# standalone.net
KiCad netlist of a schematic drawn in EAGLE
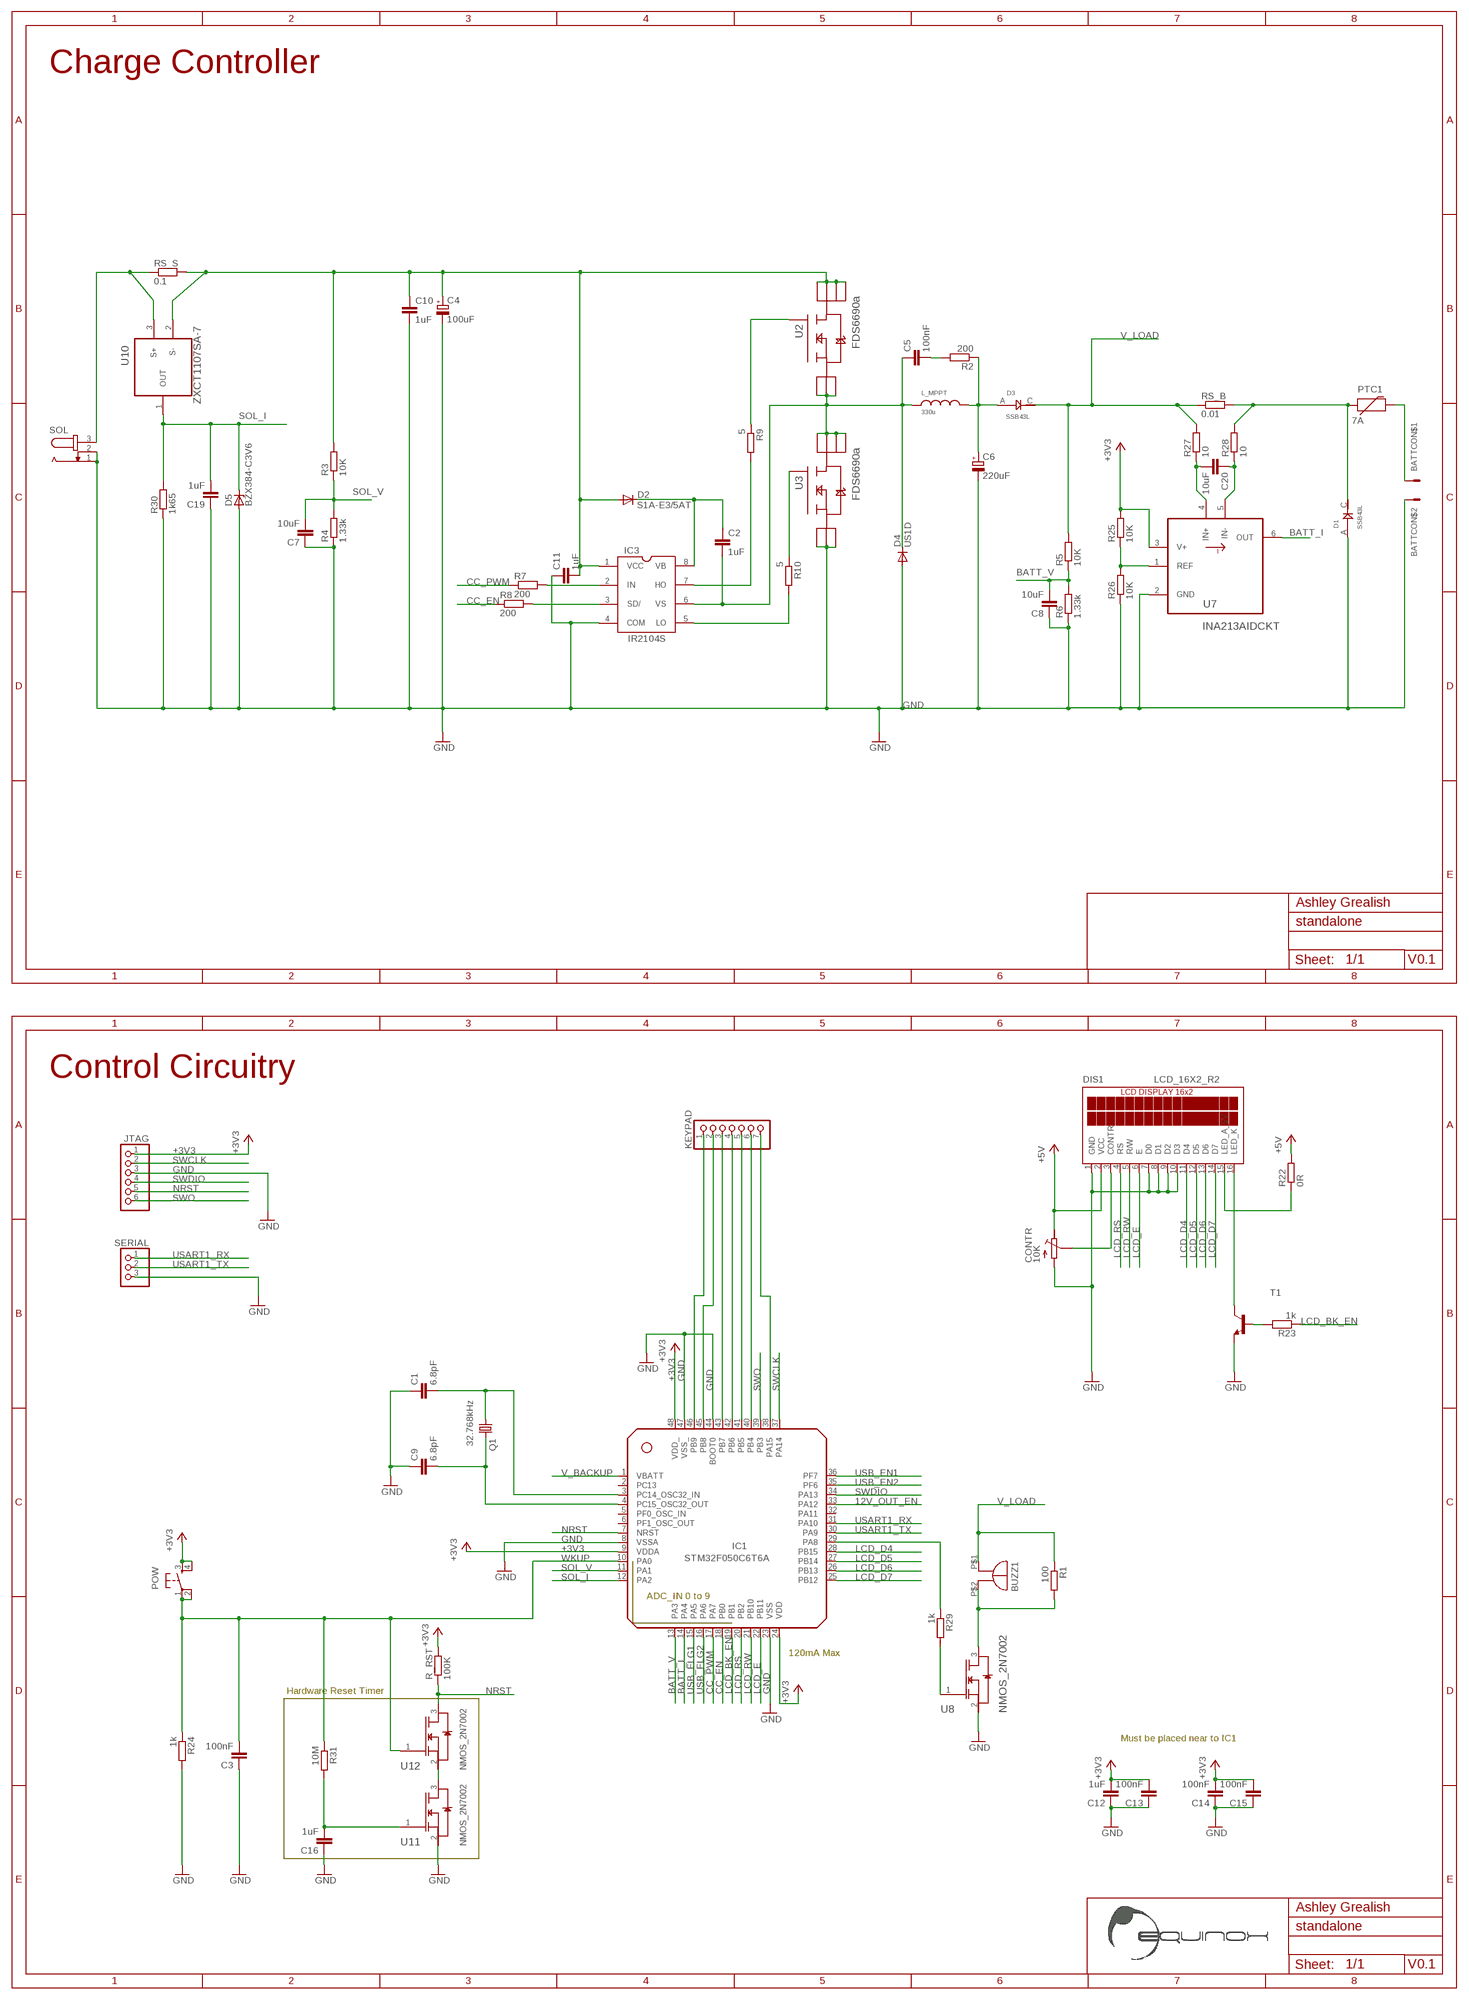
[diagram p0: schematic, sheet 1, part 1 of 2]
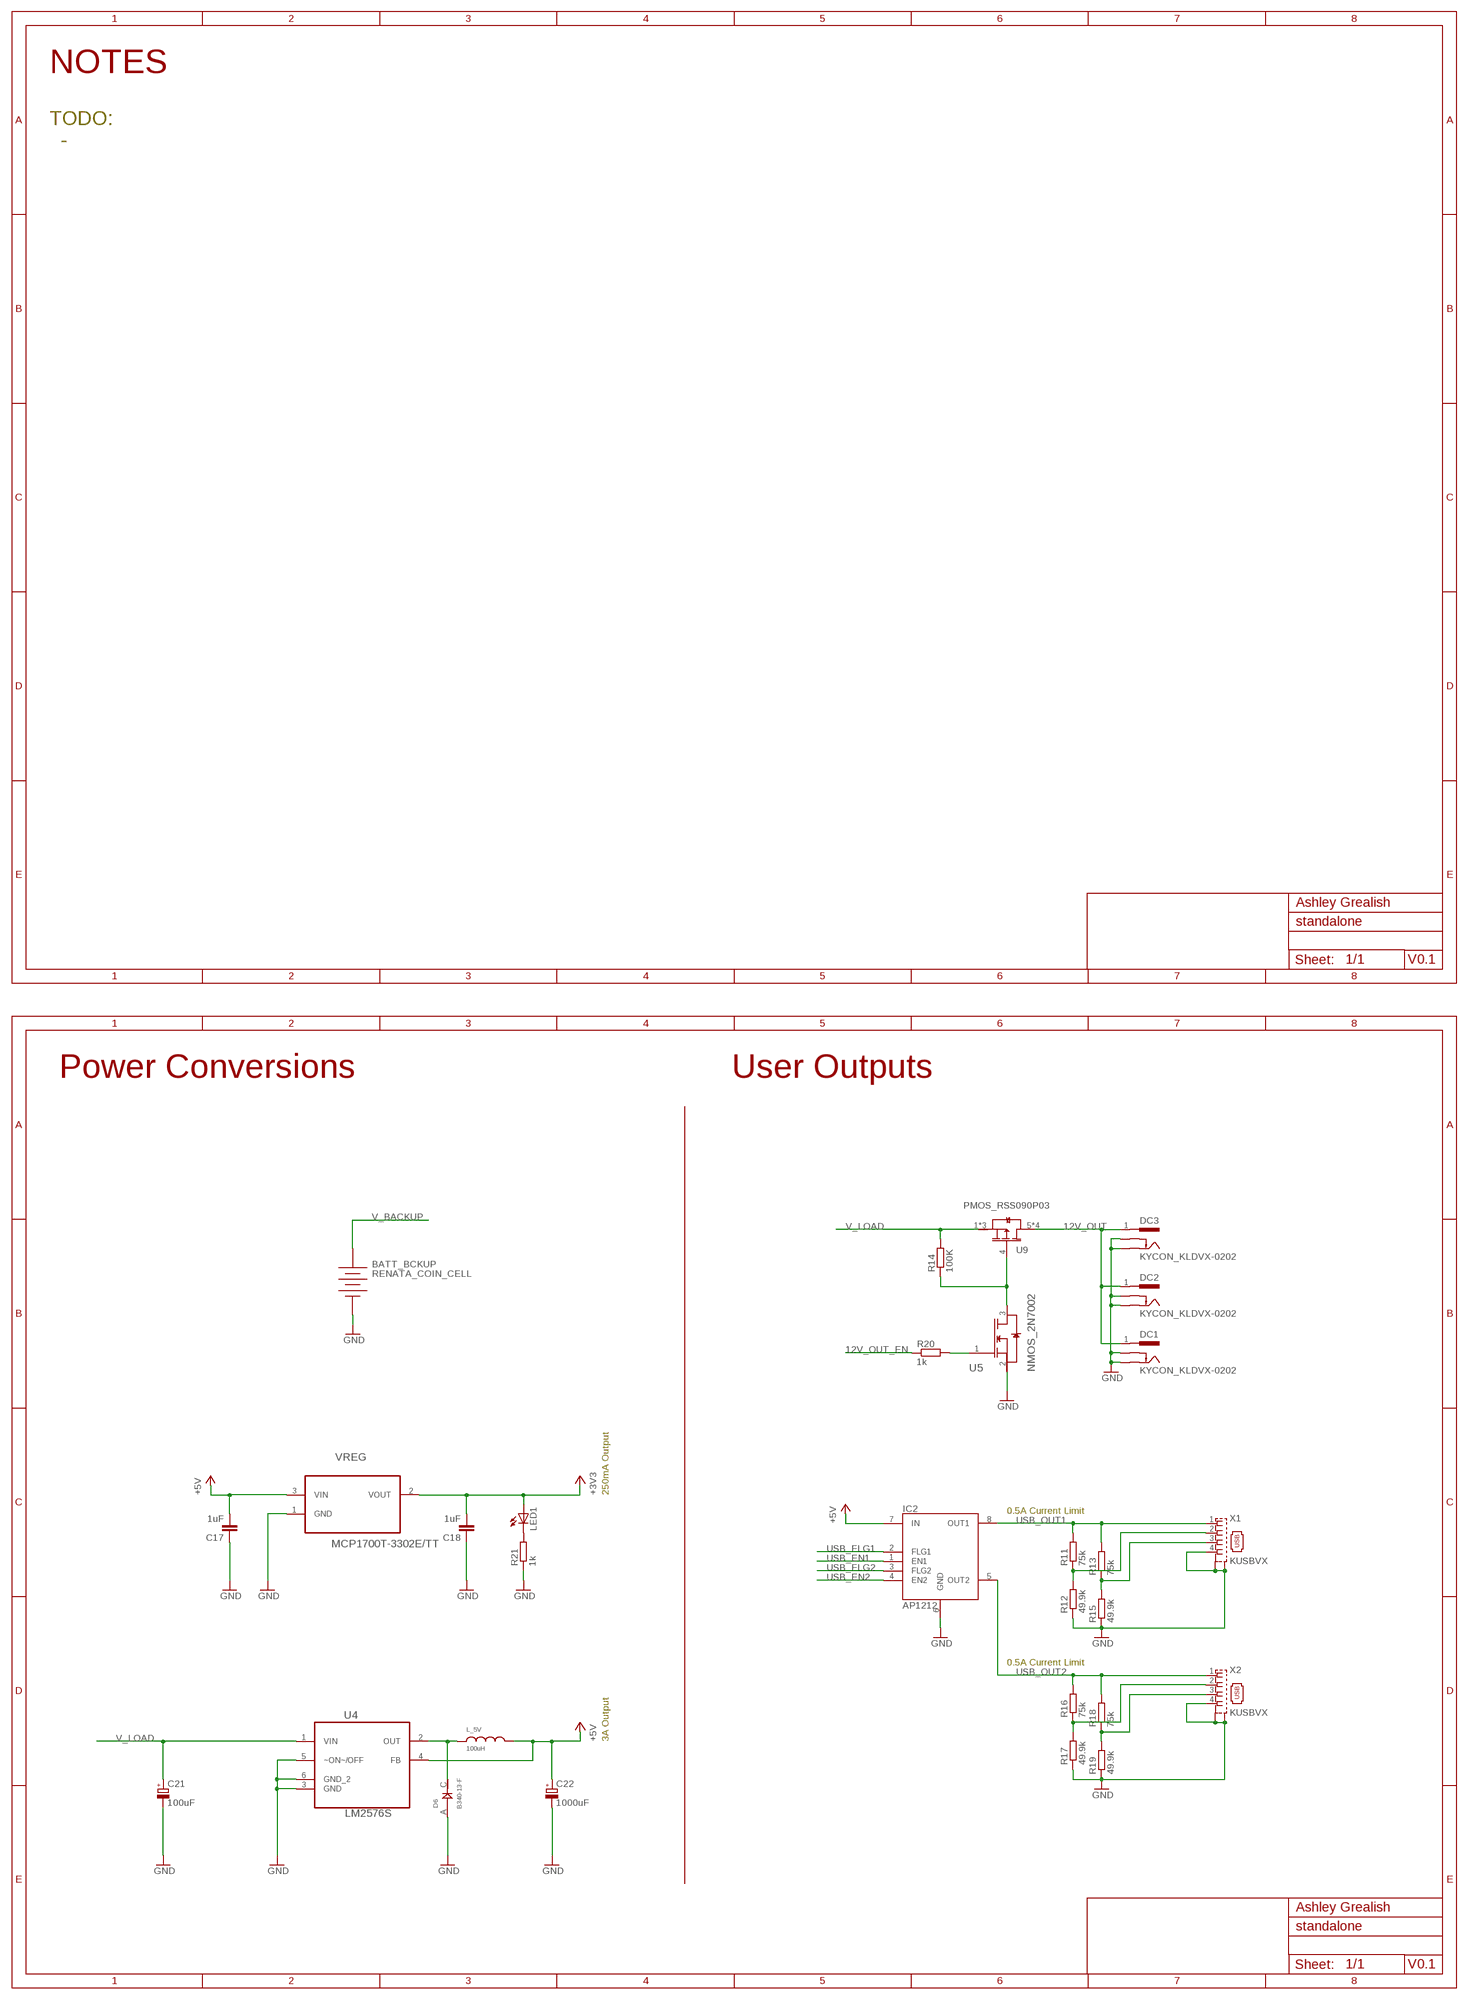
[diagram p1: schematic, sheet 1, part 2 of 2]

(export (version "E")
  (design (tool "Eeschema 10.0.6"))
  (components
    (comp (ref "BATT")
      (value "CON_MOLEX_39_29_1028")
      (footprint "eagle-import:MOLEX_39_29_1028")
      (fields (field (name "OC_FARNELL") "1012166"))
      (libsource (lib "eagle-import") (part "CON_MOLEX_39_29_1028"))
    )
    (comp (ref "BATT_BCKUP")
      (value "RENATA_COIN_CELL")
      (footprint "eagle-import:PANASONIC_CR2032_1298246")
      (libsource (lib "eagle-import") (part "PANASONIC_CR2032_1298246"))
    )
    (comp (ref "BUZZ1")
      (value "BUZZ_14MM")
      (footprint "eagle-import:BUZZ_14MM_5M_PINS")
      (libsource (lib "eagle-import") (part "BUZZ_14MM"))
    )
    (comp (ref "C1")
      (value "6.8pF")
      (footprint "eagle-import:C0603K")
      (libsource (lib "eagle-import") (part "C-EUC0603K"))
    )
    (comp (ref "C2")
      (value "1uF")
      (footprint "eagle-import:C0805K")
      (libsource (lib "eagle-import") (part "C-EUC0805K"))
    )
    (comp (ref "C3")
      (value "100nF")
      (footprint "eagle-import:C0805K")
      (libsource (lib "eagle-import") (part "C-EUC0805K"))
    )
    (comp (ref "C4")
      (value "100uF")
      (footprint "eagle-import:PANASONIC_E")
      (libsource (lib "eagle-import") (part "CPOL-EUE"))
    )
    (comp (ref "C5")
      (value "100nF")
      (footprint "eagle-import:C0805K")
      (libsource (lib "eagle-import") (part "C-EUC0805K"))
    )
    (comp (ref "C6")
      (value "220uF")
      (footprint "eagle-import:PANASONIC_F")
      (libsource (lib "eagle-import") (part "CPOL-EUF"))
    )
    (comp (ref "C7")
      (value "10uF")
      (footprint "eagle-import:C0805K")
      (libsource (lib "eagle-import") (part "C-EUC0805K"))
    )
    (comp (ref "C8")
      (value "10uF")
      (footprint "eagle-import:C0805K")
      (libsource (lib "eagle-import") (part "C-EUC0805K"))
    )
    (comp (ref "C9")
      (value "6.8pF")
      (footprint "eagle-import:C0603K")
      (libsource (lib "eagle-import") (part "C-EUC0603K"))
    )
    (comp (ref "C10")
      (value "1uF")
      (footprint "eagle-import:C0805K")
      (libsource (lib "eagle-import") (part "C-EUC0805K"))
    )
    (comp (ref "C11")
      (value "1uF")
      (footprint "eagle-import:C0805K")
      (libsource (lib "eagle-import") (part "C-EUC0805K"))
    )
    (comp (ref "C12")
      (value "1uF")
      (footprint "eagle-import:C0805K")
      (libsource (lib "eagle-import") (part "C-EUC0805K"))
    )
    (comp (ref "C13")
      (value "100nF")
      (footprint "eagle-import:C0805K")
      (libsource (lib "eagle-import") (part "C-EUC0805K"))
    )
    (comp (ref "C14")
      (value "100nF")
      (footprint "eagle-import:C0805K")
      (libsource (lib "eagle-import") (part "C-EUC0805K"))
    )
    (comp (ref "C15")
      (value "100nF")
      (footprint "eagle-import:C0805K")
      (libsource (lib "eagle-import") (part "C-EUC0805K"))
    )
    (comp (ref "C16")
      (value "1uF")
      (footprint "eagle-import:C0805K")
      (libsource (lib "eagle-import") (part "C-EUC0805K"))
    )
    (comp (ref "C17")
      (value "1uF")
      (footprint "eagle-import:C0805K")
      (libsource (lib "eagle-import") (part "C-EUC0805K"))
    )
    (comp (ref "C18")
      (value "1uF")
      (footprint "eagle-import:C0805K")
      (libsource (lib "eagle-import") (part "C-EUC0805K"))
    )
    (comp (ref "C19")
      (value "1uF")
      (footprint "eagle-import:C0805K")
      (libsource (lib "eagle-import") (part "C-EUC0805K"))
    )
    (comp (ref "C20")
      (value "10uF")
      (footprint "eagle-import:C0805K")
      (libsource (lib "eagle-import") (part "C-EUC0805K"))
    )
    (comp (ref "C21")
      (value "100uF")
      (footprint "eagle-import:PANASONIC_E")
      (libsource (lib "eagle-import") (part "CPOL-EUE"))
    )
    (comp (ref "C22")
      (value "1000uF")
      (footprint "eagle-import:PANASONIC_G")
      (libsource (lib "eagle-import") (part "CPOL-EUG"))
    )
    (comp (ref "CONTR")
      (value "10K")
      (footprint "eagle-import:R_TRIMM_RC33X")
      (libsource (lib "eagle-import") (part "R_TRIMM_TC33X"))
    )
    (comp (ref "D1")
      (value "SSB43L")
      (footprint "eagle-import:DO214AA")
      (libsource (lib "eagle-import") (part "DIODE_SSB43L"))
    )
    (comp (ref "D2")
      (value "S1A-E3/5AT")
      (footprint "eagle-import:DO-214AC")
      (libsource (lib "eagle-import") (part "DIODE-DO-214AC"))
    )
    (comp (ref "D3")
      (value "SSB43L")
      (footprint "eagle-import:DO214AA")
      (libsource (lib "eagle-import") (part "DIODE_SSB43L"))
    )
    (comp (ref "D4")
      (value "US1D")
      (footprint "eagle-import:DO-214AC")
      (libsource (lib "eagle-import") (part "DIODE-DO-214AC"))
    )
    (comp (ref "D5")
      (value "BZX384-C3V6")
      (footprint "eagle-import:SOD323")
      (libsource (lib "eagle-import") (part "BZX384-C3V6"))
    )
    (comp (ref "D6")
      (value "B340-13-F")
      (footprint "eagle-import:SMC")
      (libsource (lib "eagle-import") (part "DIODE_B340-13-F"))
    )
    (comp (ref "DC1")
      (value "KYCON_KLDVX-0202")
      (footprint "eagle-import:KYCON_KLVDX_2020_B")
      (libsource (lib "eagle-import") (part "KYCON_KLDVX-0202"))
    )
    (comp (ref "DC2")
      (value "KYCON_KLDVX-0202")
      (footprint "eagle-import:KYCON_KLVDX_2020_B")
      (libsource (lib "eagle-import") (part "KYCON_KLDVX-0202"))
    )
    (comp (ref "DC3")
      (value "KYCON_KLDVX-0202")
      (footprint "eagle-import:KYCON_KLVDX_2020_B")
      (libsource (lib "eagle-import") (part "KYCON_KLDVX-0202"))
    )
    (comp (ref "DIS1")
      (value "LCD_16X2_R2")
      (footprint "eagle-import:LCD_16X2_R2")
      (libsource (lib "eagle-import") (part "LCD_16X2_R2"))
    )
    (comp (ref "IC1")
      (value "STM32F050C6T6A")
      (footprint "eagle-import:LQFP48")
      (libsource (lib "eagle-import") (part "STM32F050C6T6A"))
    )
    (comp (ref "IC2")
      (value "AP1212")
      (footprint "eagle-import:SO8")
      (libsource (lib "eagle-import") (part "AP1212"))
    )
    (comp (ref "IC3")
      (value "IR2104S")
      (footprint "eagle-import:IR2104S")
      (libsource (lib "eagle-import") (part "IR2104S"))
    )
    (comp (ref "JTAG")
      (value "PINHD-1X6")
      (footprint "eagle-import:1X06")
      (libsource (lib "eagle-import") (part "PINHD-1X6"))
    )
    (comp (ref "KEYPAD")
      (value "PINHD-1X7/90")
      (footprint "eagle-import:1X07_90")
      (libsource (lib "eagle-import") (part "PINHD-1X7/90"))
    )
    (comp (ref "LED1")
      (value "POW_3V3")
      (footprint "eagle-import:CHIPLED_0805")
      (libsource (lib "eagle-import") (part "LEDCHIPLED_0805"))
    )
    (comp (ref "L_5V")
      (value "100uH")
      (footprint "eagle-import:INDUC_BOURNS_SDR2207")
      (libsource (lib "eagle-import") (part "INDUC_BOURNES_SDR2207"))
    )
    (comp (ref "L_MPPT")
      (value "330u")
      (footprint "eagle-import:INDUC_BOURNS_SDR1806")
      (libsource (lib "eagle-import") (part "INDUC_BOURNES_SDR1806"))
    )
    (comp (ref "POW")
      (value "TAC_SWITCHPTH")
      (footprint "eagle-import:TACTILE-PTH")
      (libsource (lib "eagle-import") (part "TAC_SWITCHPTH"))
    )
    (comp (ref "PTC1")
      (value "7A")
      (footprint "eagle-import:PTC_MF_R700")
      (libsource (lib "eagle-import") (part "PTC_MF_R700"))
    )
    (comp (ref "Q1")
      (value "32.768kHz")
      (footprint "eagle-import:MC-306")
      (fields
        (field (name "MPN") "MC-306 60.0KHZ  100PPM ,12.5PF")
        (field (name "MPN_1") "MC-306")
        (field (name "OC_FARNELL") "1712823")
        (field (name "OC_NEWARK") "-")
      )
      (libsource (lib "eagle-import") (part "MC-306"))
    )
    (comp (ref "R1")
      (value "100")
      (footprint "eagle-import:M0805")
      (libsource (lib "eagle-import") (part "resistor_R-EU_M0805"))
    )
    (comp (ref "R2")
      (value "200")
      (footprint "eagle-import:M0805")
      (libsource (lib "eagle-import") (part "R-EU_M0805"))
    )
    (comp (ref "R3")
      (value "10K")
      (footprint "eagle-import:M0805")
      (libsource (lib "eagle-import") (part "R-EU_M0805"))
    )
    (comp (ref "R4")
      (value "1.33k")
      (footprint "eagle-import:M0805")
      (libsource (lib "eagle-import") (part "R-EU_M0805"))
    )
    (comp (ref "R5")
      (value "10K")
      (footprint "eagle-import:M0805")
      (libsource (lib "eagle-import") (part "R-EU_M0805"))
    )
    (comp (ref "R6")
      (value "1.33k")
      (footprint "eagle-import:M0805")
      (libsource (lib "eagle-import") (part "R-EU_M0805"))
    )
    (comp (ref "R7")
      (value "200")
      (footprint "eagle-import:M0805")
      (libsource (lib "eagle-import") (part "R-EU_M0805"))
    )
    (comp (ref "R8")
      (value "200")
      (footprint "eagle-import:M0805")
      (libsource (lib "eagle-import") (part "R-EU_M0805"))
    )
    (comp (ref "R9")
      (value "5")
      (footprint "eagle-import:M0805")
      (libsource (lib "eagle-import") (part "R-EU_M0805"))
    )
    (comp (ref "R10")
      (value "5")
      (footprint "eagle-import:M0805")
      (libsource (lib "eagle-import") (part "R-EU_M0805"))
    )
    (comp (ref "R11")
      (value "75k")
      (footprint "eagle-import:M0805")
      (libsource (lib "eagle-import") (part "resistor_R-EU_M0805"))
    )
    (comp (ref "R12")
      (value "49.9k")
      (footprint "eagle-import:M0805")
      (libsource (lib "eagle-import") (part "resistor_R-EU_M0805"))
    )
    (comp (ref "R13")
      (value "75k")
      (footprint "eagle-import:M0805")
      (libsource (lib "eagle-import") (part "resistor_R-EU_M0805"))
    )
    (comp (ref "R14")
      (value "100K")
      (footprint "eagle-import:M0805")
      (libsource (lib "eagle-import") (part "R-EU_M0805"))
    )
    (comp (ref "R15")
      (value "49.9k")
      (footprint "eagle-import:M0805")
      (libsource (lib "eagle-import") (part "resistor_R-EU_M0805"))
    )
    (comp (ref "R16")
      (value "75k")
      (footprint "eagle-import:M0805")
      (libsource (lib "eagle-import") (part "resistor_R-EU_M0805"))
    )
    (comp (ref "R17")
      (value "49.9k")
      (footprint "eagle-import:M0805")
      (libsource (lib "eagle-import") (part "resistor_R-EU_M0805"))
    )
    (comp (ref "R18")
      (value "75k")
      (footprint "eagle-import:M0805")
      (libsource (lib "eagle-import") (part "resistor_R-EU_M0805"))
    )
    (comp (ref "R19")
      (value "49.9k")
      (footprint "eagle-import:M0805")
      (libsource (lib "eagle-import") (part "resistor_R-EU_M0805"))
    )
    (comp (ref "R20")
      (value "1k")
      (footprint "eagle-import:M0805")
      (libsource (lib "eagle-import") (part "R-EU_M0805"))
    )
    (comp (ref "R21")
      (value "1k")
      (footprint "eagle-import:M0805")
      (libsource (lib "eagle-import") (part "resistor_R-EU_M0805"))
    )
    (comp (ref "R22")
      (value "0R")
      (footprint "eagle-import:M0805")
      (libsource (lib "eagle-import") (part "resistor_R-EU_M0805"))
    )
    (comp (ref "R23")
      (value "1k")
      (footprint "eagle-import:M0805")
      (libsource (lib "eagle-import") (part "resistor_R-EU_M0805"))
    )
    (comp (ref "R24")
      (value "1k")
      (footprint "eagle-import:M0805")
      (libsource (lib "eagle-import") (part "resistor_R-EU_M0805"))
    )
    (comp (ref "R25")
      (value "10K")
      (footprint "eagle-import:M0805")
      (libsource (lib "eagle-import") (part "R-EU_M0805"))
    )
    (comp (ref "R26")
      (value "10K")
      (footprint "eagle-import:M0805")
      (libsource (lib "eagle-import") (part "R-EU_M0805"))
    )
    (comp (ref "R27")
      (value "10")
      (footprint "eagle-import:M0805")
      (libsource (lib "eagle-import") (part "R-EU_M0805"))
    )
    (comp (ref "R28")
      (value "10")
      (footprint "eagle-import:M0805")
      (libsource (lib "eagle-import") (part "R-EU_M0805"))
    )
    (comp (ref "R29")
      (value "1k")
      (footprint "eagle-import:M0805")
      (libsource (lib "eagle-import") (part "resistor_R-EU_M0805"))
    )
    (comp (ref "R30")
      (value "1k65")
      (footprint "eagle-import:M0805")
      (libsource (lib "eagle-import") (part "R-EU_M0805"))
    )
    (comp (ref "R31")
      (value "10M")
      (footprint "eagle-import:M0805")
      (libsource (lib "eagle-import") (part "resistor_R-EU_M0805"))
    )
    (comp (ref "RS_B")
      (value "0.01")
      (footprint "eagle-import:R2512")
      (libsource (lib "eagle-import") (part "R-EU_R2512"))
    )
    (comp (ref "RS_S")
      (value "0.1")
      (footprint "eagle-import:R2512")
      (libsource (lib "eagle-import") (part "R-EU_R2512"))
    )
    (comp (ref "R_RST")
      (value "100K")
      (footprint "eagle-import:M0805")
      (libsource (lib "eagle-import") (part "R-EU_M0805"))
    )
    (comp (ref "SERIAL")
      (value "PINHD-1X3")
      (footprint "eagle-import:1X03")
      (libsource (lib "eagle-import") (part "PINHD-1X3"))
    )
    (comp (ref "SOL")
      (value "JACK-PLUG0")
      (footprint "eagle-import:SPC4077")
      (libsource (lib "eagle-import") (part "JACK-PLUG0"))
    )
    (comp (ref "T1")
      (value "BC847B-NPN-SOT23-BEC")
      (footprint "eagle-import:SOT23-BEC")
      (libsource (lib "eagle-import") (part "-NPN-SOT23-BECBC847B"))
    )
    (comp (ref "U$1")
      (value "EQUINOX_LOGO_LARGE")
      (footprint "eagle-import:EQUINOX_LOGO_LARGE")
      (libsource (lib "eagle-import") (part "EQUINOX_LOGO_LARGE"))
    )
    (comp (ref "U2")
      (value "FDS6690a")
      (footprint "eagle-import:SOIC127P600X175-8N")
      (fields (field (name "MPN") "DMS3016SSS-13") (field (name "OC_FARNELL") "9845275"))
      (libsource (lib "eagle-import") (part "DMS3016SSS-13"))
    )
    (comp (ref "U3")
      (value "FDS6690a")
      (footprint "eagle-import:SOIC127P600X175-8N")
      (fields (field (name "MPN") "DMS3016SSS-13") (field (name "OC_FARNELL") "9845275 "))
      (libsource (lib "eagle-import") (part "DMS3016SSS-13"))
    )
    (comp (ref "U4")
      (value "LM2576S")
      (footprint "eagle-import:TO263-5")
      (libsource (lib "eagle-import") (part "LM2576S"))
    )
    (comp (ref "U5")
      (value "NMOS_2N7002")
      (footprint "eagle-import:SOT103P240X110-3N")
      (fields (field (name "MPN") "2N7002-7-F"))
      (libsource (lib "eagle-import") (part "NMOS_2N7002"))
    )
    (comp (ref "U7")
      (value "INA213AIDCKT")
      (footprint "eagle-import:SOT65P210X110-6N")
      (libsource (lib "eagle-import") (part "INA213AIDCKT"))
    )
    (comp (ref "U8")
      (value "NMOS_2N7002")
      (footprint "eagle-import:SOT103P240X110-3N")
      (fields
        (field (name "MPN") "2N7002-7-F")
        (field (name "MPN_1") "2N7002-7-F")
        (field (name "OC_FARNELL") "1713823")
        (field (name "OC_NEWARK") "25R5679")
        (field (name "PACKAGE") "SOT-23-3")
        (field (name "SUPPLIER") "DIODES INC.")
      )
      (libsource (lib "eagle-import") (part "NMOS_2N7002"))
    )
    (comp (ref "U9")
      (value "PMOS_RSS090P03")
      (footprint "eagle-import:SO8")
      (libsource (lib "eagle-import") (part "PMOS_RSS090P03"))
    )
    (comp (ref "U10")
      (value "ZXCT1107SA-7")
      (footprint "eagle-import:SOT91P240X110-3N")
      (libsource (lib "eagle-import") (part "ZXCT1107SA-7"))
    )
    (comp (ref "U11")
      (value "NMOS_2N7002")
      (footprint "eagle-import:SOT103P240X110-3N")
      (fields
        (field (name "MPN") "2N7002-7-F")
        (field (name "MPN_1") "2N7002-7-F")
        (field (name "OC_FARNELL") "1713823")
        (field (name "OC_NEWARK") "25R5679")
        (field (name "PACKAGE") "SOT-23-3")
        (field (name "SUPPLIER") "DIODES INC.")
      )
      (libsource (lib "eagle-import") (part "NMOS_2N7002"))
    )
    (comp (ref "U12")
      (value "NMOS_2N7002")
      (footprint "eagle-import:SOT103P240X110-3N")
      (fields
        (field (name "MPN") "2N7002-7-F")
        (field (name "MPN_1") "2N7002-7-F")
        (field (name "OC_FARNELL") "1713823")
        (field (name "OC_NEWARK") "25R5679")
        (field (name "PACKAGE") "SOT-23-3")
        (field (name "SUPPLIER") "DIODES INC.")
      )
      (libsource (lib "eagle-import") (part "NMOS_2N7002"))
    )
    (comp (ref "VREG")
      (value "MCP1700T-3302E/TT")
      (footprint "eagle-import:SOT95P237X112-3N")
      (libsource (lib "eagle-import") (part "MCP1700T-3302E/TT"))
    )
    (comp (ref "X1")
      (value "KUSBVX")
      (footprint "eagle-import:KUSBVX")
      (libsource (lib "eagle-import") (part "KUSBVX"))
    )
    (comp (ref "X2")
      (value "KUSBVX")
      (footprint "eagle-import:KUSBVX")
      (libsource (lib "eagle-import") (part "KUSBVX"))
    )
  )
  (nets
    (net (code "1") (name "+3V3") (class "Default")
      (node (ref "C12") (pin "2") (pinfunction "2_2") (pintype "passive"))
      (node (ref "C13") (pin "2") (pinfunction "2_2") (pintype "passive"))
      (node (ref "C14") (pin "2") (pinfunction "2_2") (pintype "passive"))
      (node (ref "C15") (pin "2") (pinfunction "2_2") (pintype "passive"))
      (node (ref "C18") (pin "2") (pinfunction "2_2") (pintype "passive"))
      (node (ref "IC1") (pin "24") (pinfunction "VDD_24") (pintype "power_in"))
      (node (ref "IC1") (pin "48") (pinfunction "VDD__48") (pintype "power_in"))
      (node (ref "IC1") (pin "9") (pinfunction "VDDA_9") (pintype "bidirectional"))
      (node (ref "JTAG") (pin "1") (pinfunction "1_1") (pintype "passive"))
      (node (ref "LED1") (pin "A") (pinfunction "A_A") (pintype "passive"))
      (node (ref "POW") (pin "3") (pinfunction "3_3") (pintype "passive"))
      (node (ref "POW") (pin "4") (pinfunction "4_4") (pintype "passive"))
      (node (ref "R25") (pin "2") (pinfunction "2_2") (pintype "passive"))
      (node (ref "R_RST") (pin "2") (pinfunction "2_2") (pintype "passive"))
      (node (ref "U7") (pin "3") (pinfunction "V+_3") (pintype "power_in"))
      (node (ref "VREG") (pin "2") (pinfunction "VOUT_2") (pintype "output"))
    )
    (net (code "2") (name "+5V") (class "Default")
      (node (ref "C17") (pin "2") (pinfunction "2_2") (pintype "passive"))
      (node (ref "C22") (pin "+") (pinfunction "+_+") (pintype "passive"))
      (node (ref "CONTR") (pin "CW") (pinfunction "A_CW") (pintype "passive"))
      (node (ref "DIS1") (pin "2") (pinfunction "VCC_2") (pintype "power_in"))
      (node (ref "IC2") (pin "7") (pinfunction "IN_7") (pintype "bidirectional"))
      (node (ref "L_5V") (pin "P$2") (pinfunction "P$2_P$2") (pintype "bidirectional"))
      (node (ref "R22") (pin "2") (pinfunction "2_2") (pintype "passive"))
      (node (ref "U4") (pin "4") (pinfunction "FB_4") (pintype "bidirectional"))
      (node (ref "VREG") (pin "3") (pinfunction "VIN_3") (pintype "input"))
    )
    (net (code "3") (name "/12V_OUT") (class "Default")
      (node (ref "DC1") (pin "1") (pinfunction "PAD1_1") (pintype "passive"))
      (node (ref "DC2") (pin "1") (pinfunction "PAD1_1") (pintype "passive"))
      (node (ref "DC3") (pin "1") (pinfunction "PAD1_1") (pintype "passive"))
      (node (ref "U9") (pin "5") (pinfunction "D2_5") (pintype "bidirectional"))
      (node (ref "U9") (pin "6") (pinfunction "D2_6") (pintype "bidirectional"))
      (node (ref "U9") (pin "7") (pinfunction "D2_7") (pintype "bidirectional"))
      (node (ref "U9") (pin "8") (pinfunction "D2_8") (pintype "bidirectional"))
    )
    (net (code "4") (name "/12V_OUT_EN") (class "Default")
      (node (ref "IC1") (pin "33") (pinfunction "PA12_33") (pintype "bidirectional"))
      (node (ref "R20") (pin "1") (pinfunction "1_1") (pintype "passive"))
    )
    (net (code "5") (name "/BATT_I") (class "Default")
      (node (ref "IC1") (pin "14") (pinfunction "PA4_14") (pintype "bidirectional"))
      (node (ref "U7") (pin "6") (pinfunction "OUT_6") (pintype "output"))
    )
    (net (code "6") (name "/BATT_V") (class "Default")
      (node (ref "C8") (pin "2") (pinfunction "2_2") (pintype "passive"))
      (node (ref "IC1") (pin "13") (pinfunction "PA3_13") (pintype "bidirectional"))
      (node (ref "R5") (pin "1") (pinfunction "1_1") (pintype "passive"))
      (node (ref "R6") (pin "2") (pinfunction "2_2") (pintype "passive"))
    )
    (net (code "7") (name "/CC_EN") (class "Default")
      (node (ref "IC1") (pin "18") (pinfunction "PB0_18") (pintype "bidirectional"))
      (node (ref "R8") (pin "1") (pinfunction "1_1") (pintype "passive"))
    )
    (net (code "8") (name "/CC_PWM") (class "Default")
      (node (ref "IC1") (pin "17") (pinfunction "PA7_17") (pintype "bidirectional"))
      (node (ref "R7") (pin "1") (pinfunction "1_1") (pintype "passive"))
    )
    (net (code "9") (name "/LCD_BK_EN") (class "Default")
      (node (ref "IC1") (pin "19") (pinfunction "PB1_19") (pintype "bidirectional"))
      (node (ref "R23") (pin "1") (pinfunction "1_1") (pintype "passive"))
    )
    (net (code "10") (name "/LCD_D4") (class "Default")
      (node (ref "DIS1") (pin "11") (pinfunction "D4_11") (pintype "input"))
      (node (ref "IC1") (pin "28") (pinfunction "PB15_28") (pintype "bidirectional"))
    )
    (net (code "11") (name "/LCD_D5") (class "Default")
      (node (ref "DIS1") (pin "12") (pinfunction "D5_12") (pintype "input"))
      (node (ref "IC1") (pin "27") (pinfunction "PB14_27") (pintype "bidirectional"))
    )
    (net (code "12") (name "/LCD_D6") (class "Default")
      (node (ref "DIS1") (pin "13") (pinfunction "D6_13") (pintype "input"))
      (node (ref "IC1") (pin "26") (pinfunction "PB13_26") (pintype "bidirectional"))
    )
    (net (code "13") (name "/LCD_D7") (class "Default")
      (node (ref "DIS1") (pin "14") (pinfunction "D7_14") (pintype "input"))
      (node (ref "IC1") (pin "25") (pinfunction "PB12_25") (pintype "bidirectional"))
    )
    (net (code "14") (name "/LCD_E") (class "Default")
      (node (ref "DIS1") (pin "6") (pinfunction "E_6") (pintype "input"))
      (node (ref "IC1") (pin "22") (pinfunction "PB11_22") (pintype "bidirectional"))
    )
    (net (code "15") (name "/LCD_RS") (class "Default")
      (node (ref "DIS1") (pin "4") (pinfunction "RS_4") (pintype "input"))
      (node (ref "IC1") (pin "20") (pinfunction "PB2_20") (pintype "bidirectional"))
    )
    (net (code "16") (name "/LCD_RW") (class "Default")
      (node (ref "DIS1") (pin "5") (pinfunction "R/W_5") (pintype "input"))
      (node (ref "IC1") (pin "21") (pinfunction "PB10_21") (pintype "bidirectional"))
    )
    (net (code "17") (name "/NRST") (class "Default")
      (node (ref "IC1") (pin "7") (pinfunction "NRST_7") (pintype "bidirectional"))
      (node (ref "JTAG") (pin "5") (pinfunction "5_5") (pintype "passive"))
      (node (ref "R_RST") (pin "1") (pinfunction "1_1") (pintype "passive"))
      (node (ref "U12") (pin "3") (pinfunction "D_3") (pintype "output"))
    )
    (net (code "18") (name "/SOL_I") (class "Default")
      (node (ref "C19") (pin "2") (pinfunction "2_2") (pintype "passive"))
      (node (ref "D5") (pin "C") (pinfunction "C_C") (pintype "passive"))
      (node (ref "IC1") (pin "12") (pinfunction "PA2_12") (pintype "bidirectional"))
      (node (ref "R30") (pin "2") (pinfunction "2_2") (pintype "passive"))
      (node (ref "U10") (pin "1") (pinfunction "OUT_1") (pintype "output"))
    )
    (net (code "19") (name "/SOL_V") (class "Default")
      (node (ref "C7") (pin "2") (pinfunction "2_2") (pintype "passive"))
      (node (ref "IC1") (pin "11") (pinfunction "PA1_11") (pintype "bidirectional"))
      (node (ref "R3") (pin "1") (pinfunction "1_1") (pintype "passive"))
      (node (ref "R4") (pin "2") (pinfunction "2_2") (pintype "passive"))
    )
    (net (code "20") (name "/SWCLK") (class "Default")
      (node (ref "IC1") (pin "37") (pinfunction "PA14_37") (pintype "bidirectional"))
      (node (ref "JTAG") (pin "2") (pinfunction "2_2") (pintype "passive"))
    )
    (net (code "21") (name "/SWDIO") (class "Default")
      (node (ref "IC1") (pin "34") (pinfunction "PA13_34") (pintype "bidirectional"))
      (node (ref "JTAG") (pin "4") (pinfunction "4_4") (pintype "passive"))
    )
    (net (code "22") (name "/SWO") (class "Default")
      (node (ref "IC1") (pin "39") (pinfunction "PB3_39") (pintype "bidirectional"))
      (node (ref "JTAG") (pin "6") (pinfunction "6_6") (pintype "passive"))
    )
    (net (code "23") (name "/USART1_RX") (class "Default")
      (node (ref "IC1") (pin "31") (pinfunction "PA10_31") (pintype "bidirectional"))
      (node (ref "SERIAL") (pin "1") (pinfunction "1_1") (pintype "passive"))
    )
    (net (code "24") (name "/USART1_TX") (class "Default")
      (node (ref "IC1") (pin "30") (pinfunction "PA9_30") (pintype "bidirectional"))
      (node (ref "SERIAL") (pin "2") (pinfunction "2_2") (pintype "passive"))
    )
    (net (code "25") (name "/USB_EN1") (class "Default")
      (node (ref "IC1") (pin "36") (pinfunction "PF7_36") (pintype "bidirectional"))
      (node (ref "IC2") (pin "1") (pinfunction "EN1_1") (pintype "bidirectional"))
    )
    (net (code "26") (name "/USB_EN2") (class "Default")
      (node (ref "IC1") (pin "35") (pinfunction "PF6_35") (pintype "bidirectional"))
      (node (ref "IC2") (pin "4") (pinfunction "EN2_4") (pintype "bidirectional"))
    )
    (net (code "27") (name "/USB_FLG1") (class "Default")
      (node (ref "IC1") (pin "15") (pinfunction "PA5_15") (pintype "bidirectional"))
      (node (ref "IC2") (pin "2") (pinfunction "FLG1_2") (pintype "bidirectional"))
    )
    (net (code "28") (name "/USB_FLG2") (class "Default")
      (node (ref "IC1") (pin "16") (pinfunction "PA6_16") (pintype "bidirectional"))
      (node (ref "IC2") (pin "3") (pinfunction "FLG2_3") (pintype "bidirectional"))
    )
    (net (code "29") (name "/USB_OUT1") (class "Default")
      (node (ref "IC2") (pin "8") (pinfunction "OUT1_8") (pintype "bidirectional"))
      (node (ref "R11") (pin "2") (pinfunction "2_2") (pintype "passive"))
      (node (ref "R13") (pin "2") (pinfunction "2_2") (pintype "passive"))
      (node (ref "X1") (pin "1") (pinfunction "1_1") (pintype "passive"))
    )
    (net (code "30") (name "/USB_OUT2") (class "Default")
      (node (ref "IC2") (pin "5") (pinfunction "OUT2_5") (pintype "bidirectional"))
      (node (ref "R16") (pin "2") (pinfunction "2_2") (pintype "passive"))
      (node (ref "R18") (pin "2") (pinfunction "2_2") (pintype "passive"))
      (node (ref "X2") (pin "1") (pinfunction "1_1") (pintype "passive"))
    )
    (net (code "31") (name "/V_BACKUP") (class "Default")
      (node (ref "BATT_BCKUP") (pin "P+") (pinfunction "POS_P+") (pintype "bidirectional"))
      (node (ref "IC1") (pin "1") (pinfunction "VBATT_1") (pintype "bidirectional"))
    )
    (net (code "32") (name "/V_LOAD") (class "Default")
      (node (ref "BUZZ1") (pin "P$1") (pinfunction "+_P$1") (pintype "passive"))
      (node (ref "C21") (pin "+") (pinfunction "+_+") (pintype "passive"))
      (node (ref "D3") (pin "C") (pinfunction "CATHODE_C") (pintype "bidirectional"))
      (node (ref "R1") (pin "1") (pinfunction "1_1") (pintype "passive"))
      (node (ref "R14") (pin "2") (pinfunction "2_2") (pintype "passive"))
      (node (ref "R27") (pin "2") (pinfunction "2_2") (pintype "passive"))
      (node (ref "R5") (pin "2") (pinfunction "2_2") (pintype "passive"))
      (node (ref "RS_B") (pin "1") (pinfunction "1_1") (pintype "passive"))
      (node (ref "U4") (pin "1") (pinfunction "VIN_1") (pintype "input"))
      (node (ref "U9") (pin "1") (pinfunction "S2_1") (pintype "bidirectional"))
      (node (ref "U9") (pin "2") (pinfunction "S2_2") (pintype "bidirectional"))
      (node (ref "U9") (pin "3") (pinfunction "S2_3") (pintype "bidirectional"))
    )
    (net (code "33") (name "/WKUP") (class "Default")
      (node (ref "C3") (pin "2") (pinfunction "2_2") (pintype "passive"))
      (node (ref "IC1") (pin "10") (pinfunction "PA0_10") (pintype "bidirectional"))
      (node (ref "POW") (pin "1") (pinfunction "1_1") (pintype "passive"))
      (node (ref "POW") (pin "2") (pinfunction "2_2") (pintype "passive"))
      (node (ref "R24") (pin "1") (pinfunction "1_1") (pintype "passive"))
      (node (ref "R31") (pin "1") (pinfunction "1_1") (pintype "passive"))
      (node (ref "U12") (pin "1") (pinfunction "G_1") (pintype "input"))
    )
    (net (code "34") (name "GND") (class "Default")
      (node (ref "BATT") (pin "P$2") (pinfunction "S_P$2") (pintype "passive"))
      (node (ref "BATT_BCKUP") (pin "P-") (pinfunction "NEG_P-") (pintype "bidirectional"))
      (node (ref "C1") (pin "1") (pinfunction "1_1") (pintype "passive"))
      (node (ref "C10") (pin "2") (pinfunction "2_2") (pintype "passive"))
      (node (ref "C11") (pin "1") (pinfunction "1_1") (pintype "passive"))
      (node (ref "C12") (pin "1") (pinfunction "1_1") (pintype "passive"))
      (node (ref "C13") (pin "1") (pinfunction "1_1") (pintype "passive"))
      (node (ref "C14") (pin "1") (pinfunction "1_1") (pintype "passive"))
      (node (ref "C15") (pin "1") (pinfunction "1_1") (pintype "passive"))
      (node (ref "C16") (pin "1") (pinfunction "1_1") (pintype "passive"))
      (node (ref "C17") (pin "1") (pinfunction "1_1") (pintype "passive"))
      (node (ref "C18") (pin "1") (pinfunction "1_1") (pintype "passive"))
      (node (ref "C19") (pin "1") (pinfunction "1_1") (pintype "passive"))
      (node (ref "C21") (pin "-") (pinfunction "-_-") (pintype "passive"))
      (node (ref "C22") (pin "-") (pinfunction "-_-") (pintype "passive"))
      (node (ref "C3") (pin "1") (pinfunction "1_1") (pintype "passive"))
      (node (ref "C4") (pin "-") (pinfunction "-_-") (pintype "passive"))
      (node (ref "C6") (pin "-") (pinfunction "-_-") (pintype "passive"))
      (node (ref "C7") (pin "1") (pinfunction "1_1") (pintype "passive"))
      (node (ref "C8") (pin "1") (pinfunction "1_1") (pintype "passive"))
      (node (ref "C9") (pin "1") (pinfunction "1_1") (pintype "passive"))
      (node (ref "CONTR") (pin "CCW") (pinfunction "E_CCW") (pintype "passive"))
      (node (ref "D1") (pin "A") (pinfunction "ANODE_A") (pintype "bidirectional"))
      (node (ref "D4") (pin "A") (pinfunction "A_A") (pintype "passive"))
      (node (ref "D5") (pin "A") (pinfunction "A_A") (pintype "passive"))
      (node (ref "D6") (pin "A") (pinfunction "ANODE_A") (pintype "bidirectional"))
      (node (ref "DC1") (pin "2") (pinfunction "PAD2_2") (pintype "passive"))
      (node (ref "DC1") (pin "3") (pinfunction "PAD3_3") (pintype "passive"))
      (node (ref "DC2") (pin "2") (pinfunction "PAD2_2") (pintype "passive"))
      (node (ref "DC2") (pin "3") (pinfunction "PAD3_3") (pintype "passive"))
      (node (ref "DC3") (pin "2") (pinfunction "PAD2_2") (pintype "passive"))
      (node (ref "DC3") (pin "3") (pinfunction "PAD3_3") (pintype "passive"))
      (node (ref "DIS1") (pin "1") (pinfunction "GND_1") (pintype "power_in"))
      (node (ref "DIS1") (pin "10") (pinfunction "D3_10") (pintype "input"))
      (node (ref "DIS1") (pin "7") (pinfunction "D0_7") (pintype "input"))
      (node (ref "DIS1") (pin "8") (pinfunction "D1_8") (pintype "input"))
      (node (ref "DIS1") (pin "9") (pinfunction "D2_9") (pintype "input"))
      (node (ref "IC1") (pin "23") (pinfunction "VSS_23") (pintype "power_in"))
      (node (ref "IC1") (pin "44") (pinfunction "BOOT0_44") (pintype "bidirectional"))
      (node (ref "IC1") (pin "47") (pinfunction "VSS__47") (pintype "power_in"))
      (node (ref "IC1") (pin "8") (pinfunction "VSSA_8") (pintype "bidirectional"))
      (node (ref "IC2") (pin "6") (pinfunction "GND_6") (pintype "power_in"))
      (node (ref "IC3") (pin "4") (pinfunction "COM_4") (pintype "bidirectional"))
      (node (ref "JTAG") (pin "3") (pinfunction "3_3") (pintype "passive"))
      (node (ref "R12") (pin "1") (pinfunction "1_1") (pintype "passive"))
      (node (ref "R15") (pin "1") (pinfunction "1_1") (pintype "passive"))
      (node (ref "R17") (pin "1") (pinfunction "1_1") (pintype "passive"))
      (node (ref "R19") (pin "1") (pinfunction "1_1") (pintype "passive"))
      (node (ref "R21") (pin "1") (pinfunction "1_1") (pintype "passive"))
      (node (ref "R24") (pin "2") (pinfunction "2_2") (pintype "passive"))
      (node (ref "R26") (pin "1") (pinfunction "1_1") (pintype "passive"))
      (node (ref "R30") (pin "1") (pinfunction "1_1") (pintype "passive"))
      (node (ref "R4") (pin "1") (pinfunction "1_1") (pintype "passive"))
      (node (ref "R6") (pin "1") (pinfunction "1_1") (pintype "passive"))
      (node (ref "SERIAL") (pin "3") (pinfunction "3_3") (pintype "passive"))
      (node (ref "SOL") (pin "1") (pinfunction "1_1") (pintype "passive"))
      (node (ref "SOL") (pin "2") (pinfunction "2_2") (pintype "passive"))
      (node (ref "T1") (pin "E") (pinfunction "E_E") (pintype "passive"))
      (node (ref "U11") (pin "2") (pinfunction "S_2") (pintype "passive"))
      (node (ref "U3") (pin "1") (pinfunction "S_2_1") (pintype "passive"))
      (node (ref "U3") (pin "2") (pinfunction "S_3_2") (pintype "passive"))
      (node (ref "U3") (pin "3") (pinfunction "S_3") (pintype "passive"))
      (node (ref "U4") (pin "3") (pinfunction "GND_3") (pintype "passive"))
      (node (ref "U4") (pin "5") (pinfunction "~{ON}/OFF_5") (pintype "passive"))
      (node (ref "U4") (pin "6") (pinfunction "GND_2_6") (pintype "passive"))
      (node (ref "U5") (pin "2") (pinfunction "S_2") (pintype "passive"))
      (node (ref "U7") (pin "2") (pinfunction "GND_2") (pintype "passive"))
      (node (ref "U8") (pin "2") (pinfunction "S_2") (pintype "passive"))
      (node (ref "VREG") (pin "1") (pinfunction "GND_1") (pintype "passive"))
      (node (ref "X1") (pin "4") (pinfunction "4_4") (pintype "passive"))
      (node (ref "X1") (pin "M1") (pinfunction "S1_M1") (pintype "passive"))
      (node (ref "X1") (pin "M2") (pinfunction "S2_M2") (pintype "passive"))
      (node (ref "X2") (pin "4") (pinfunction "4_4") (pintype "passive"))
      (node (ref "X2") (pin "M1") (pinfunction "S1_M1") (pintype "passive"))
      (node (ref "X2") (pin "M2") (pinfunction "S2_M2") (pintype "passive"))
    )
    (net (code "35") (name "Net-(BATTA-S)") (class "Default")
      (node (ref "BATT") (pin "P$1") (pinfunction "S_P$1") (pintype "passive"))
      (node (ref "PTC1") (pin "P$2") (pinfunction "P$2_P$2") (pintype "bidirectional"))
    )
    (net (code "36") (name "Net-(BUZZ1--)") (class "Default")
      (node (ref "BUZZ1") (pin "P$2") (pinfunction "-_P$2") (pintype "passive"))
      (node (ref "R1") (pin "2") (pinfunction "2_2") (pintype "passive"))
      (node (ref "U8") (pin "3") (pinfunction "D_3") (pintype "output"))
    )
    (net (code "37") (name "Net-(C5-Pad2)") (class "Default")
      (node (ref "C5") (pin "2") (pinfunction "2_2") (pintype "passive"))
      (node (ref "R2") (pin "2") (pinfunction "2_2") (pintype "passive"))
    )
    (net (code "38") (name "Net-(CONTR-S)") (class "Default")
      (node (ref "CONTR") (pin "WIPE") (pinfunction "S_WIPE") (pintype "passive"))
      (node (ref "DIS1") (pin "3") (pinfunction "CONTR_3") (pintype "input"))
    )
    (net (code "39") (name "Net-(D1-CATHODE)") (class "Default")
      (node (ref "D1") (pin "C") (pinfunction "CATHODE_C") (pintype "bidirectional"))
      (node (ref "PTC1") (pin "P$1") (pinfunction "P$1_P$1") (pintype "bidirectional"))
      (node (ref "R28") (pin "2") (pinfunction "2_2") (pintype "passive"))
      (node (ref "RS_B") (pin "2") (pinfunction "2_2") (pintype "passive"))
    )
    (net (code "40") (name "Net-(D3-ANODE)") (class "Default")
      (node (ref "C6") (pin "+") (pinfunction "+_+") (pintype "passive"))
      (node (ref "D3") (pin "A") (pinfunction "ANODE_A") (pintype "bidirectional"))
      (node (ref "L_MPPT") (pin "P$2") (pinfunction "P$2_P$2") (pintype "bidirectional"))
      (node (ref "R2") (pin "1") (pinfunction "1_1") (pintype "passive"))
    )
    (net (code "41") (name "Net-(D6-CATHODE)") (class "Default")
      (node (ref "D6") (pin "C") (pinfunction "CATHODE_C") (pintype "bidirectional"))
      (node (ref "L_5V") (pin "P$1") (pinfunction "P$1_P$1") (pintype "bidirectional"))
      (node (ref "U4") (pin "2") (pinfunction "OUT_2") (pintype "output"))
    )
    (net (code "42") (name "Net-(DIS1-LED_A_5V)") (class "Default")
      (node (ref "DIS1") (pin "15") (pinfunction "LED_A_5V_15") (pintype "bidirectional"))
      (node (ref "R22") (pin "1") (pinfunction "1_1") (pintype "passive"))
    )
    (net (code "43") (name "Net-(DIS1-LED_K)") (class "Default")
      (node (ref "DIS1") (pin "16") (pinfunction "LED_K_16") (pintype "bidirectional"))
      (node (ref "T1") (pin "C") (pinfunction "C_C") (pintype "passive"))
    )
    (net (code "44") (name "Net-(IC1-PA8)") (class "Default")
      (node (ref "IC1") (pin "29") (pinfunction "PA8_29") (pintype "bidirectional"))
      (node (ref "R29") (pin "1") (pinfunction "1_1") (pintype "passive"))
    )
    (net (code "45") (name "Net-(IC1-PA15)") (class "Default")
      (node (ref "IC1") (pin "38") (pinfunction "PA15_38") (pintype "bidirectional"))
      (node (ref "KEYPAD") (pin "7") (pinfunction "7_7") (pintype "passive"))
    )
    (net (code "46") (name "Net-(IC1-PB4)") (class "Default")
      (node (ref "IC1") (pin "40") (pinfunction "PB4_40") (pintype "bidirectional"))
      (node (ref "KEYPAD") (pin "6") (pinfunction "6_6") (pintype "passive"))
    )
    (net (code "47") (name "Net-(IC1-PB5)") (class "Default")
      (node (ref "IC1") (pin "41") (pinfunction "PB5_41") (pintype "bidirectional"))
      (node (ref "KEYPAD") (pin "5") (pinfunction "5_5") (pintype "passive"))
    )
    (net (code "48") (name "Net-(IC1-PB6)") (class "Default")
      (node (ref "IC1") (pin "42") (pinfunction "PB6_42") (pintype "bidirectional"))
      (node (ref "KEYPAD") (pin "4") (pinfunction "4_4") (pintype "passive"))
    )
    (net (code "49") (name "Net-(IC1-PB7)") (class "Default")
      (node (ref "IC1") (pin "43") (pinfunction "PB7_43") (pintype "bidirectional"))
      (node (ref "KEYPAD") (pin "3") (pinfunction "3_3") (pintype "passive"))
    )
    (net (code "50") (name "Net-(IC1-PB8)") (class "Default")
      (node (ref "IC1") (pin "45") (pinfunction "PB8_45") (pintype "bidirectional"))
      (node (ref "KEYPAD") (pin "2") (pinfunction "2_2") (pintype "passive"))
    )
    (net (code "51") (name "Net-(IC1-PB9)") (class "Default")
      (node (ref "IC1") (pin "46") (pinfunction "PB9_46") (pintype "bidirectional"))
      (node (ref "KEYPAD") (pin "1") (pinfunction "1_1") (pintype "passive"))
    )
    (net (code "52") (name "Net-(IC1-PC14_OSC32_IN)") (class "Default")
      (node (ref "C1") (pin "2") (pinfunction "2_2") (pintype "passive"))
      (node (ref "IC1") (pin "3") (pinfunction "PC14_OSC32_IN_3") (pintype "bidirectional"))
      (node (ref "Q1") (pin "1") (pinfunction "1_1") (pintype "passive"))
    )
    (net (code "53") (name "Net-(IC1-PC15_OSC32_OUT)") (class "Default")
      (node (ref "C9") (pin "2") (pinfunction "2_2") (pintype "passive"))
      (node (ref "IC1") (pin "4") (pinfunction "PC15_OSC32_OUT_4") (pintype "bidirectional"))
      (node (ref "Q1") (pin "4") (pinfunction "2_4") (pintype "passive"))
    )
    (net (code "54") (name "Net-(IC3-HO)") (class "Default")
      (node (ref "IC3") (pin "7") (pinfunction "HO_7") (pintype "bidirectional"))
      (node (ref "R9") (pin "2") (pinfunction "2_2") (pintype "passive"))
    )
    (net (code "55") (name "Net-(IC3-IN)") (class "Default")
      (node (ref "IC3") (pin "2") (pinfunction "IN_2") (pintype "bidirectional"))
      (node (ref "R7") (pin "2") (pinfunction "2_2") (pintype "passive"))
    )
    (net (code "56") (name "Net-(IC3-LO)") (class "Default")
      (node (ref "IC3") (pin "5") (pinfunction "LO_5") (pintype "bidirectional"))
      (node (ref "R10") (pin "2") (pinfunction "2_2") (pintype "passive"))
    )
    (net (code "57") (name "Net-(IC3-SD{slash})") (class "Default")
      (node (ref "IC3") (pin "3") (pinfunction "SD/_3") (pintype "bidirectional"))
      (node (ref "R8") (pin "2") (pinfunction "2_2") (pintype "passive"))
    )
    (net (code "58") (name "Net-(IC3-VB)") (class "Default")
      (node (ref "C2") (pin "1") (pinfunction "1_1") (pintype "passive"))
      (node (ref "D2") (pin "C") (pinfunction "C_C") (pintype "passive"))
      (node (ref "IC3") (pin "8") (pinfunction "VB_8") (pintype "power_in"))
    )
    (net (code "59") (name "Net-(IC3-VCC)") (class "Default")
      (node (ref "C10") (pin "1") (pinfunction "1_1") (pintype "passive"))
      (node (ref "C11") (pin "2") (pinfunction "2_2") (pintype "passive"))
      (node (ref "C4") (pin "+") (pinfunction "+_+") (pintype "passive"))
      (node (ref "D2") (pin "A") (pinfunction "A_A") (pintype "passive"))
      (node (ref "IC3") (pin "1") (pinfunction "VCC_1") (pintype "power_in"))
      (node (ref "R3") (pin "2") (pinfunction "2_2") (pintype "passive"))
      (node (ref "RS_S") (pin "2") (pinfunction "2_2") (pintype "passive"))
      (node (ref "U10") (pin "2") (pinfunction "S-_2") (pintype "input"))
      (node (ref "U2") (pin "5") (pinfunction "D_3_5") (pintype "passive"))
      (node (ref "U2") (pin "6") (pinfunction "D_2_6") (pintype "passive"))
      (node (ref "U2") (pin "7") (pinfunction "D_4_7") (pintype "passive"))
      (node (ref "U2") (pin "8") (pinfunction "D_8") (pintype "passive"))
    )
    (net (code "60") (name "Net-(IC3-VS)") (class "Default")
      (node (ref "C2") (pin "2") (pinfunction "2_2") (pintype "passive"))
      (node (ref "C5") (pin "1") (pinfunction "1_1") (pintype "passive"))
      (node (ref "D4") (pin "C") (pinfunction "C_C") (pintype "passive"))
      (node (ref "IC3") (pin "6") (pinfunction "VS_6") (pintype "power_in"))
      (node (ref "L_MPPT") (pin "P$1") (pinfunction "P$1_P$1") (pintype "bidirectional"))
      (node (ref "U2") (pin "1") (pinfunction "S_2_1") (pintype "passive"))
      (node (ref "U2") (pin "2") (pinfunction "S_3_2") (pintype "passive"))
      (node (ref "U2") (pin "3") (pinfunction "S_3") (pintype "passive"))
      (node (ref "U3") (pin "5") (pinfunction "D_3_5") (pintype "passive"))
      (node (ref "U3") (pin "6") (pinfunction "D_2_6") (pintype "passive"))
      (node (ref "U3") (pin "7") (pinfunction "D_4_7") (pintype "passive"))
      (node (ref "U3") (pin "8") (pinfunction "D_8") (pintype "passive"))
    )
    (net (code "61") (name "Net-(LED1-PadC)") (class "Default")
      (node (ref "LED1") (pin "C") (pinfunction "C_C") (pintype "passive"))
      (node (ref "R21") (pin "2") (pinfunction "2_2") (pintype "passive"))
    )
    (net (code "62") (name "Net-(R11-Pad1)") (class "Default")
      (node (ref "R11") (pin "1") (pinfunction "1_1") (pintype "passive"))
      (node (ref "R12") (pin "2") (pinfunction "2_2") (pintype "passive"))
      (node (ref "X1") (pin "2") (pinfunction "2_2") (pintype "passive"))
    )
    (net (code "63") (name "Net-(R13-Pad1)") (class "Default")
      (node (ref "R13") (pin "1") (pinfunction "1_1") (pintype "passive"))
      (node (ref "R15") (pin "2") (pinfunction "2_2") (pintype "passive"))
      (node (ref "X1") (pin "3") (pinfunction "3_3") (pintype "passive"))
    )
    (net (code "64") (name "Net-(R16-Pad1)") (class "Default")
      (node (ref "R16") (pin "1") (pinfunction "1_1") (pintype "passive"))
      (node (ref "R17") (pin "2") (pinfunction "2_2") (pintype "passive"))
      (node (ref "X2") (pin "2") (pinfunction "2_2") (pintype "passive"))
    )
    (net (code "65") (name "Net-(R18-Pad1)") (class "Default")
      (node (ref "R18") (pin "1") (pinfunction "1_1") (pintype "passive"))
      (node (ref "R19") (pin "2") (pinfunction "2_2") (pintype "passive"))
      (node (ref "X2") (pin "3") (pinfunction "3_3") (pintype "passive"))
    )
    (net (code "66") (name "Net-(R23-Pad2)") (class "Default")
      (node (ref "R23") (pin "2") (pinfunction "2_2") (pintype "passive"))
      (node (ref "T1") (pin "B") (pinfunction "B_B") (pintype "passive"))
    )
    (net (code "67") (name "Net-(U2-G)") (class "Default")
      (node (ref "R9") (pin "1") (pinfunction "1_1") (pintype "passive"))
      (node (ref "U2") (pin "4") (pinfunction "G_4") (pintype "passive"))
    )
    (net (code "68") (name "Net-(U3-G)") (class "Default")
      (node (ref "R10") (pin "1") (pinfunction "1_1") (pintype "passive"))
      (node (ref "U3") (pin "4") (pinfunction "G_4") (pintype "passive"))
    )
    (net (code "69") (name "Net-(U5-D)") (class "Default")
      (node (ref "R14") (pin "1") (pinfunction "1_1") (pintype "passive"))
      (node (ref "U5") (pin "3") (pinfunction "D_3") (pintype "output"))
      (node (ref "U9") (pin "4") (pinfunction "G_4") (pintype "bidirectional"))
    )
    (net (code "70") (name "Net-(U5-G)") (class "Default")
      (node (ref "R20") (pin "2") (pinfunction "2_2") (pintype "passive"))
      (node (ref "U5") (pin "1") (pinfunction "G_1") (pintype "input"))
    )
    (net (code "71") (name "Net-(U7-IN+)") (class "Default")
      (node (ref "C20") (pin "2") (pinfunction "2_2") (pintype "passive"))
      (node (ref "R27") (pin "1") (pinfunction "1_1") (pintype "passive"))
      (node (ref "U7") (pin "4") (pinfunction "IN+_4") (pintype "input"))
    )
    (net (code "72") (name "Net-(U7-IN-)") (class "Default")
      (node (ref "C20") (pin "1") (pinfunction "1_1") (pintype "passive"))
      (node (ref "R28") (pin "1") (pinfunction "1_1") (pintype "passive"))
      (node (ref "U7") (pin "5") (pinfunction "IN-_5") (pintype "input"))
    )
    (net (code "73") (name "Net-(U7-REF)") (class "Default")
      (node (ref "R25") (pin "1") (pinfunction "1_1") (pintype "passive"))
      (node (ref "R26") (pin "2") (pinfunction "2_2") (pintype "passive"))
      (node (ref "U7") (pin "1") (pinfunction "REF_1") (pintype "input"))
    )
    (net (code "74") (name "Net-(U8-G)") (class "Default")
      (node (ref "R29") (pin "2") (pinfunction "2_2") (pintype "passive"))
      (node (ref "U8") (pin "1") (pinfunction "G_1") (pintype "input"))
    )
    (net (code "75") (name "Net-(U10-S+)") (class "Default")
      (node (ref "RS_S") (pin "1") (pinfunction "1_1") (pintype "passive"))
      (node (ref "SOL") (pin "3") (pinfunction "3_3") (pintype "passive"))
      (node (ref "U10") (pin "3") (pinfunction "S+_3") (pintype "input"))
    )
    (net (code "76") (name "Net-(U11-D)") (class "Default")
      (node (ref "U11") (pin "3") (pinfunction "D_3") (pintype "output"))
      (node (ref "U12") (pin "2") (pinfunction "S_2") (pintype "passive"))
    )
    (net (code "77") (name "Net-(U11-G)") (class "Default")
      (node (ref "C16") (pin "2") (pinfunction "2_2") (pintype "passive"))
      (node (ref "R31") (pin "2") (pinfunction "2_2") (pintype "passive"))
      (node (ref "U11") (pin "1") (pinfunction "G_1") (pintype "input"))
    )
    (net (code "78") (name "unconnected-(IC1-PA11-Pad32)") (class "Default")
      (node (ref "IC1") (pin "32") (pinfunction "PA11_32") (pintype "bidirectional"))
    )
    (net (code "79") (name "unconnected-(IC1-PC13-Pad2)") (class "Default")
      (node (ref "IC1") (pin "2") (pinfunction "PC13_2") (pintype "bidirectional"))
    )
    (net (code "80") (name "unconnected-(IC1-PF0_OSC_IN-Pad5)") (class "Default")
      (node (ref "IC1") (pin "5") (pinfunction "PF0_OSC_IN_5") (pintype "bidirectional"))
    )
    (net (code "81") (name "unconnected-(IC1-PF1_OSC_OUT-Pad6)") (class "Default")
      (node (ref "IC1") (pin "6") (pinfunction "PF1_OSC_OUT_6") (pintype "input"))
    )
  )
)
